# mon.net
KiCad netlist of a schematic drawn in EAGLE
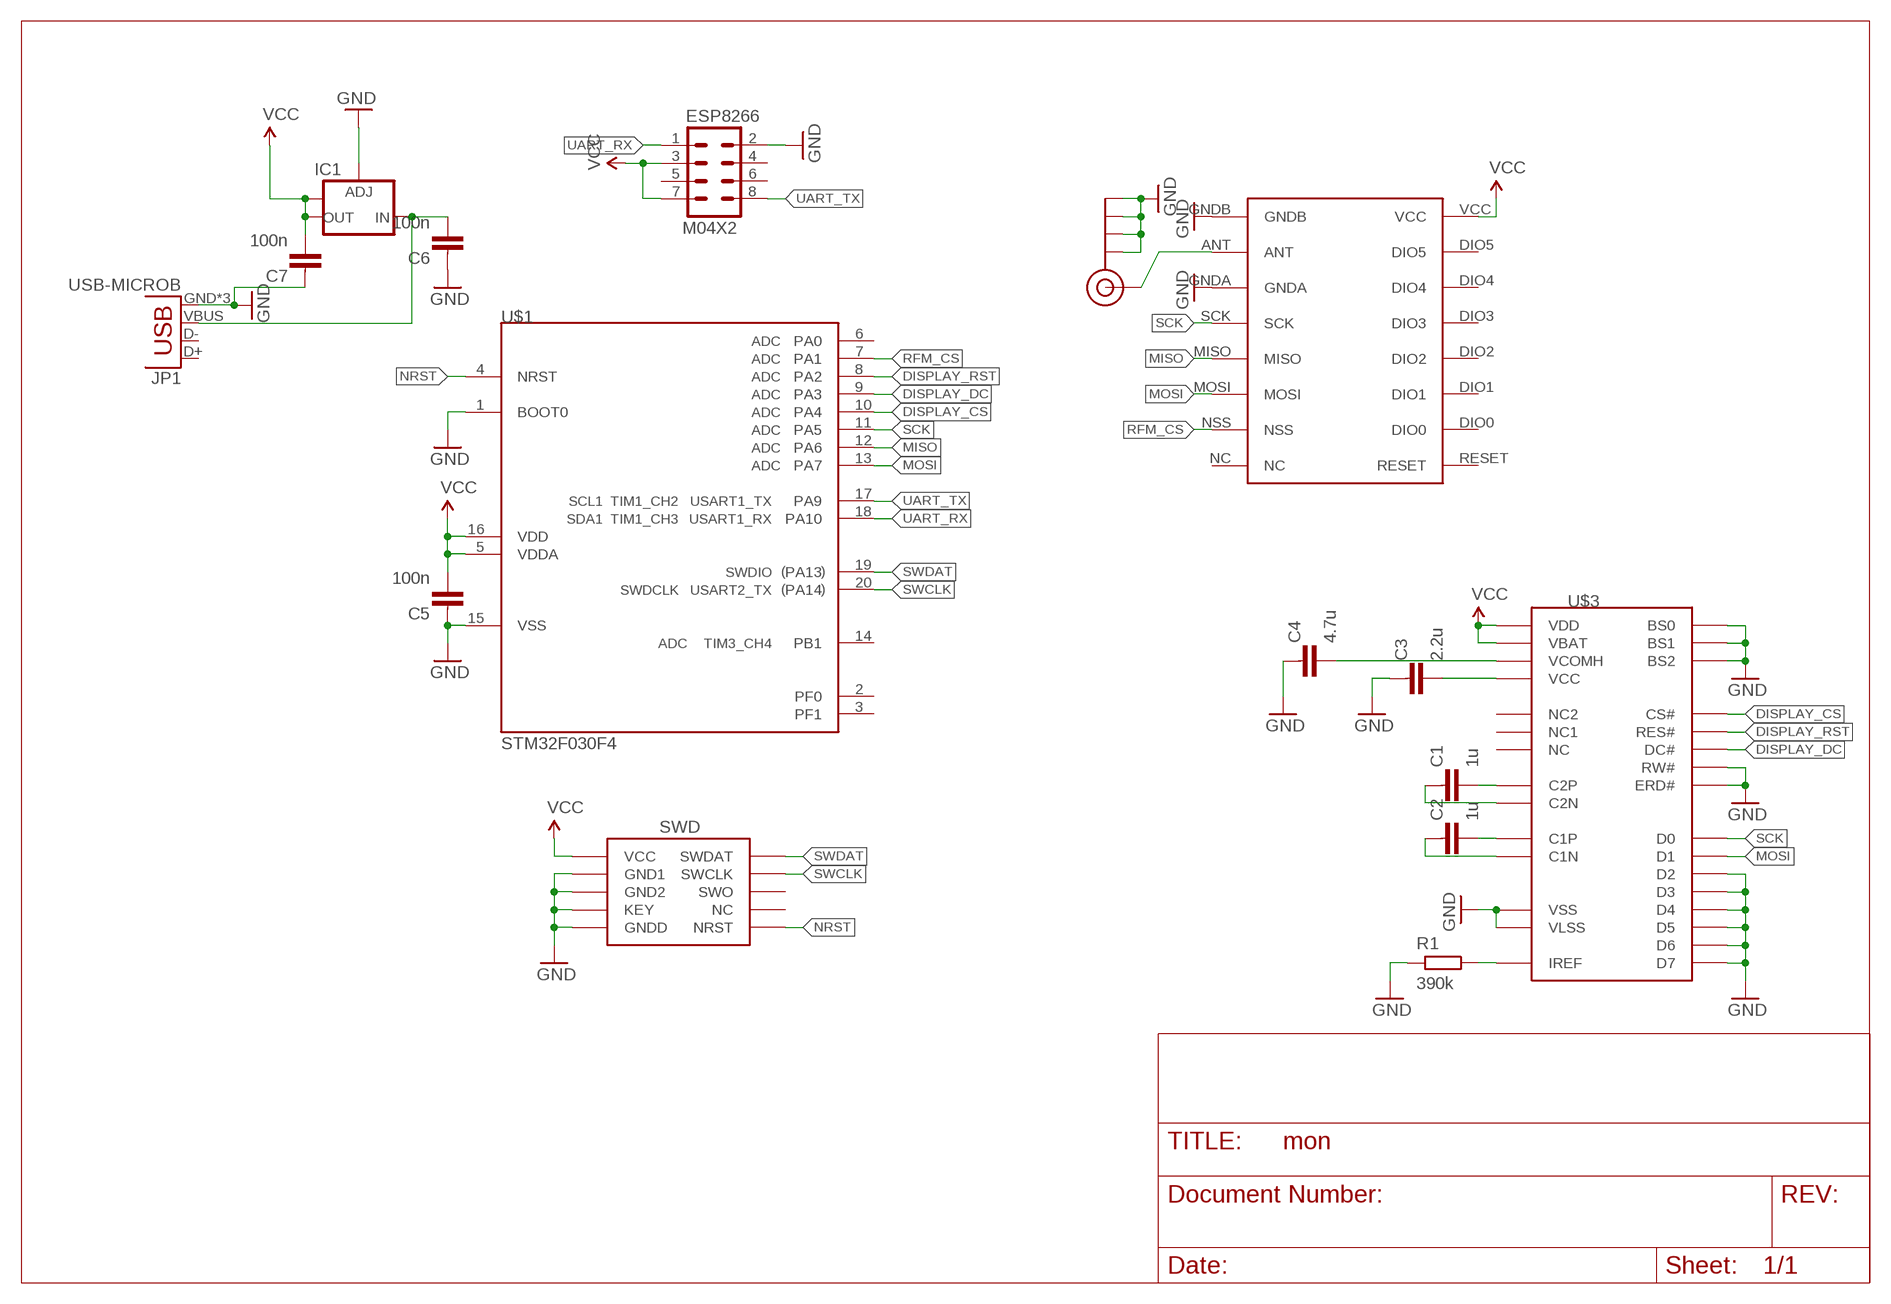
[diagram p0: schematic, sheet 1]

(export (version "E")
  (design (tool "Eeschema 10.0.6"))
  (components
    (comp (ref "C1")
      (value "1u")
      (footprint "eagle-import:C0603-L")
      (libsource (lib "eagle-import") (part "CAPACITOR0603-L"))
    )
    (comp (ref "C2")
      (value "1u")
      (footprint "eagle-import:C0603-L")
      (libsource (lib "eagle-import") (part "CAPACITOR0603-L"))
    )
    (comp (ref "C3")
      (value "2.2u")
      (footprint "eagle-import:C0603-L")
      (libsource (lib "eagle-import") (part "CAPACITOR0603-L"))
    )
    (comp (ref "C4")
      (value "4.7u")
      (footprint "eagle-import:C0603-L")
      (libsource (lib "eagle-import") (part "CAPACITOR0603-L"))
    )
    (comp (ref "C5")
      (value "100n")
      (footprint "eagle-import:C0603-L")
      (libsource (lib "eagle-import") (part "CAPACITOR0603-L"))
    )
    (comp (ref "C6")
      (value "100n")
      (footprint "eagle-import:C0603-L")
      (libsource (lib "eagle-import") (part "CAPACITOR0603-L"))
    )
    (comp (ref "C7")
      (value "100n")
      (footprint "eagle-import:C0603-L")
      (libsource (lib "eagle-import") (part "CAPACITOR0603-L"))
    )
    (comp (ref "ESP8266")
      (value "M04X2")
      (footprint "eagle-import:2X4")
      (libsource (lib "eagle-import") (part "M04X2"))
    )
    (comp (ref "IC1")
      (value "V_REG_LM1117SOT223")
      (footprint "eagle-import:SOT223")
      (libsource (lib "eagle-import") (part "V_REG_LM1117SOT223"))
    )
    (comp (ref "J$1")
      (value "SMA_EDGE")
      (footprint "eagle-import:SMA-EDGE")
      (libsource (lib "eagle-import") (part "SMA_EDGE"))
    )
    (comp (ref "JP1")
      (value "USB-MICROB")
      (footprint "eagle-import:USB-MICROB")
      (libsource (lib "eagle-import") (part "USB-MICROB"))
    )
    (comp (ref "R1")
      (value "390k")
      (footprint "eagle-import:R0603-L")
      (libsource (lib "eagle-import") (part "RESISTOR0603-L"))
    )
    (comp (ref "U$1")
      (value "STM32F030F4")
      (footprint "eagle-import:TSSOP20")
      (libsource (lib "eagle-import") (part "STM32F030F4"))
    )
    (comp (ref "U$2")
      (value "RFM69HW")
      (footprint "eagle-import:RFM")
      (libsource (lib "eagle-import") (part "RFM69HW"))
    )
    (comp (ref "U$3")
      (value "096_INCH_MONOCHROME_DISP")
      (footprint "eagle-import:096_INCH_MONOCHROME_DISP")
      (libsource (lib "eagle-import") (part "096_INCH_MONOCHROME_DISP"))
    )
    (comp (ref "U$4")
      (value "SWD_SHROUD_SMD")
      (footprint "eagle-import:SWD_SMD_SHROUD")
      (libsource (lib "eagle-import") (part "SWD_SHROUD_SMD"))
    )
  )
  (nets
    (net (code "1") (name "DISPLAY_CS") (class "Default")
      (node (ref "U$1") (pin "10") (pinfunction "PA4_10") (pintype "bidirectional"))
      (node (ref "U$3") (pin "P$13") (pinfunction "CS#_P$13") (pintype "bidirectional"))
    )
    (net (code "2") (name "DISPLAY_DC") (class "Default")
      (node (ref "U$1") (pin "9") (pinfunction "PA3_9") (pintype "bidirectional"))
      (node (ref "U$3") (pin "P$15") (pinfunction "DC#_P$15") (pintype "bidirectional"))
    )
    (net (code "3") (name "DISPLAY_RST") (class "Default")
      (node (ref "U$1") (pin "8") (pinfunction "PA2_8") (pintype "bidirectional"))
      (node (ref "U$3") (pin "P$14") (pinfunction "RES#_P$14") (pintype "bidirectional"))
    )
    (net (code "4") (name "GND") (class "Default")
      (node (ref "C3") (pin "1") (pinfunction "1_1") (pintype "passive"))
      (node (ref "C4") (pin "1") (pinfunction "1_1") (pintype "passive"))
      (node (ref "C5") (pin "1") (pinfunction "1_1") (pintype "passive"))
      (node (ref "C6") (pin "1") (pinfunction "1_1") (pintype "passive"))
      (node (ref "C7") (pin "1") (pinfunction "1_1") (pintype "passive"))
      (node (ref "ESP8266") (pin "2") (pinfunction "2_2") (pintype "passive"))
      (node (ref "IC1") (pin "1") (pinfunction "ADJ_1") (pintype "input"))
      (node (ref "J$1") (pin "GND@0") (pinfunction "GND_GND@0") (pintype "bidirectional"))
      (node (ref "J$1") (pin "GND@1") (pinfunction "GND_GND@1") (pintype "bidirectional"))
      (node (ref "J$1") (pin "GND@2") (pinfunction "GND_GND@2") (pintype "bidirectional"))
      (node (ref "J$1") (pin "GND@3") (pinfunction "GND_GND@3") (pintype "bidirectional"))
      (node (ref "JP1") (pin "GND") (pinfunction "GND_GND") (pintype "bidirectional"))
      (node (ref "JP1") (pin "MT1") (pinfunction "GND_MT1") (pintype "bidirectional"))
      (node (ref "JP1") (pin "MT2") (pinfunction "GND_MT2") (pintype "bidirectional"))
      (node (ref "R1") (pin "1") (pinfunction "P$1_1") (pintype "passive"))
      (node (ref "U$1") (pin "1") (pinfunction "BOOT0_1") (pintype "input"))
      (node (ref "U$1") (pin "15") (pinfunction "VSS_15") (pintype "power_in"))
      (node (ref "U$2") (pin "GNDA") (pinfunction "GNDA_GNDA") (pintype "bidirectional"))
      (node (ref "U$2") (pin "GNDB") (pinfunction "GNDB_GNDB") (pintype "bidirectional"))
      (node (ref "U$3") (pin "P$10") (pinfunction "BS0_P$10") (pintype "bidirectional"))
      (node (ref "U$3") (pin "P$11") (pinfunction "BS1_P$11") (pintype "bidirectional"))
      (node (ref "U$3") (pin "P$12") (pinfunction "BS2_P$12") (pintype "bidirectional"))
      (node (ref "U$3") (pin "P$16") (pinfunction "RW#_P$16") (pintype "bidirectional"))
      (node (ref "U$3") (pin "P$17") (pinfunction "ERD#_P$17") (pintype "bidirectional"))
      (node (ref "U$3") (pin "P$20") (pinfunction "D2_P$20") (pintype "bidirectional"))
      (node (ref "U$3") (pin "P$21") (pinfunction "D3_P$21") (pintype "bidirectional"))
      (node (ref "U$3") (pin "P$22") (pinfunction "D4_P$22") (pintype "bidirectional"))
      (node (ref "U$3") (pin "P$23") (pinfunction "D5_P$23") (pintype "bidirectional"))
      (node (ref "U$3") (pin "P$24") (pinfunction "D6_P$24") (pintype "bidirectional"))
      (node (ref "U$3") (pin "P$25") (pinfunction "D7_P$25") (pintype "bidirectional"))
      (node (ref "U$3") (pin "P$29") (pinfunction "VLSS_P$29") (pintype "bidirectional"))
      (node (ref "U$3") (pin "P$8") (pinfunction "VSS_P$8") (pintype "bidirectional"))
      (node (ref "U$4") (pin "3") (pinfunction "GND1_3") (pintype "power_in"))
      (node (ref "U$4") (pin "5") (pinfunction "GND2_5") (pintype "power_in"))
      (node (ref "U$4") (pin "7") (pinfunction "KEY_7") (pintype "bidirectional"))
      (node (ref "U$4") (pin "9") (pinfunction "GNDD_9") (pintype "power_in"))
    )
    (net (code "5") (name "MISO") (class "Default")
      (node (ref "U$1") (pin "12") (pinfunction "PA6_12") (pintype "bidirectional"))
      (node (ref "U$2") (pin "MISO") (pinfunction "MISO_MISO") (pintype "bidirectional"))
    )
    (net (code "6") (name "MOSI") (class "Default")
      (node (ref "U$1") (pin "13") (pinfunction "PA7_13") (pintype "bidirectional"))
      (node (ref "U$2") (pin "MOSI") (pinfunction "MOSI_MOSI") (pintype "bidirectional"))
      (node (ref "U$3") (pin "P$19") (pinfunction "D1_P$19") (pintype "bidirectional"))
    )
    (net (code "7") (name "NRST") (class "Default")
      (node (ref "U$1") (pin "4") (pinfunction "NRST_4") (pintype "input"))
      (node (ref "U$4") (pin "10") (pinfunction "NRST_10") (pintype "bidirectional"))
    )
    (net (code "8") (name "Net-(IC1-IN)") (class "Default")
      (node (ref "C6") (pin "2") (pinfunction "2_2") (pintype "passive"))
      (node (ref "IC1") (pin "3") (pinfunction "IN_3") (pintype "input"))
      (node (ref "JP1") (pin "VBUS") (pinfunction "VBUS_VBUS") (pintype "bidirectional"))
    )
    (net (code "9") (name "Net-(J$1-SIGNAL)") (class "Default")
      (node (ref "J$1") (pin "SIG") (pinfunction "SIGNAL_SIG") (pintype "bidirectional"))
      (node (ref "U$2") (pin "ANT") (pinfunction "ANT_ANT") (pintype "bidirectional"))
    )
    (net (code "10") (name "Net-(R1-P$2)") (class "Default")
      (node (ref "R1") (pin "2") (pinfunction "P$2_2") (pintype "passive"))
      (node (ref "U$3") (pin "P$26") (pinfunction "IREF_P$26") (pintype "bidirectional"))
    )
    (net (code "11") (name "Net-(U$3-C1N)") (class "Default")
      (node (ref "C2") (pin "1") (pinfunction "1_1") (pintype "passive"))
      (node (ref "U$3") (pin "P$5") (pinfunction "C1N_P$5") (pintype "bidirectional"))
    )
    (net (code "12") (name "Net-(U$3-C1P)") (class "Default")
      (node (ref "C2") (pin "2") (pinfunction "2_2") (pintype "passive"))
      (node (ref "U$3") (pin "P$4") (pinfunction "C1P_P$4") (pintype "bidirectional"))
    )
    (net (code "13") (name "Net-(U$3-C2N)") (class "Default")
      (node (ref "C1") (pin "1") (pinfunction "1_1") (pintype "passive"))
      (node (ref "U$3") (pin "P$3") (pinfunction "C2N_P$3") (pintype "bidirectional"))
    )
    (net (code "14") (name "Net-(U$3-C2P)") (class "Default")
      (node (ref "C1") (pin "2") (pinfunction "2_2") (pintype "passive"))
      (node (ref "U$3") (pin "P$2") (pinfunction "C2P_P$2") (pintype "bidirectional"))
    )
    (net (code "15") (name "Net-(U$3-VCC)") (class "Default")
      (node (ref "C3") (pin "2") (pinfunction "2_2") (pintype "passive"))
      (node (ref "U$3") (pin "P$28") (pinfunction "VCC_P$28") (pintype "bidirectional"))
    )
    (net (code "16") (name "Net-(U$3-VCOMH)") (class "Default")
      (node (ref "C4") (pin "2") (pinfunction "2_2") (pintype "passive"))
      (node (ref "U$3") (pin "P$27") (pinfunction "VCOMH_P$27") (pintype "bidirectional"))
    )
    (net (code "17") (name "RFM_CS") (class "Default")
      (node (ref "U$1") (pin "7") (pinfunction "PA1_7") (pintype "bidirectional"))
      (node (ref "U$2") (pin "NSS") (pinfunction "NSS_NSS") (pintype "bidirectional"))
    )
    (net (code "18") (name "SCK") (class "Default")
      (node (ref "U$1") (pin "11") (pinfunction "PA5_11") (pintype "bidirectional"))
      (node (ref "U$2") (pin "SCK") (pinfunction "SCK_SCK") (pintype "bidirectional"))
      (node (ref "U$3") (pin "P$18") (pinfunction "D0_P$18") (pintype "bidirectional"))
    )
    (net (code "19") (name "SWCLK") (class "Default")
      (node (ref "U$1") (pin "20") (pinfunction "PA14_20") (pintype "bidirectional"))
      (node (ref "U$4") (pin "4") (pinfunction "SWCLK_4") (pintype "bidirectional"))
    )
    (net (code "20") (name "SWDAT") (class "Default")
      (node (ref "U$1") (pin "19") (pinfunction "PA13_19") (pintype "bidirectional"))
      (node (ref "U$4") (pin "2") (pinfunction "SWDAT_2") (pintype "bidirectional"))
    )
    (net (code "21") (name "UART_RX") (class "Default")
      (node (ref "ESP8266") (pin "1") (pinfunction "1_1") (pintype "passive"))
      (node (ref "U$1") (pin "18") (pinfunction "PA10_18") (pintype "bidirectional"))
    )
    (net (code "22") (name "UART_TX") (class "Default")
      (node (ref "ESP8266") (pin "8") (pinfunction "8_8") (pintype "passive"))
      (node (ref "U$1") (pin "17") (pinfunction "PA9_17") (pintype "bidirectional"))
    )
    (net (code "23") (name "VCC") (class "Default")
      (node (ref "C5") (pin "2") (pinfunction "2_2") (pintype "passive"))
      (node (ref "C7") (pin "2") (pinfunction "2_2") (pintype "passive"))
      (node (ref "ESP8266") (pin "3") (pinfunction "3_3") (pintype "passive"))
      (node (ref "ESP8266") (pin "7") (pinfunction "7_7") (pintype "passive"))
      (node (ref "IC1") (pin "2") (pinfunction "OUT_2") (pintype "output"))
      (node (ref "IC1") (pin "4") (pinfunction "OUT_4") (pintype "output"))
      (node (ref "U$1") (pin "16") (pinfunction "VDD_16") (pintype "power_in"))
      (node (ref "U$1") (pin "5") (pinfunction "VDDA_5") (pintype "power_in"))
      (node (ref "U$2") (pin "VCC") (pinfunction "VCC_VCC") (pintype "bidirectional"))
      (node (ref "U$3") (pin "P$6") (pinfunction "VBAT_P$6") (pintype "bidirectional"))
      (node (ref "U$3") (pin "P$9") (pinfunction "VDD_P$9") (pintype "bidirectional"))
      (node (ref "U$4") (pin "1") (pinfunction "VCC_1") (pintype "power_in"))
    )
    (net (code "24") (name "unconnected-(ESP8266-Pad4)") (class "Default")
      (node (ref "ESP8266") (pin "4") (pinfunction "4_4") (pintype "passive"))
    )
    (net (code "25") (name "unconnected-(ESP8266-Pad5)") (class "Default")
      (node (ref "ESP8266") (pin "5") (pinfunction "5_5") (pintype "passive"))
    )
    (net (code "26") (name "unconnected-(ESP8266-Pad6)") (class "Default")
      (node (ref "ESP8266") (pin "6") (pinfunction "6_6") (pintype "passive"))
    )
    (net (code "27") (name "unconnected-(JP1-PadD+)") (class "Default")
      (node (ref "JP1") (pin "D+") (pinfunction "D+_D+") (pintype "bidirectional"))
    )
    (net (code "28") (name "unconnected-(JP1-PadD-)") (class "Default")
      (node (ref "JP1") (pin "D-") (pinfunction "D-_D-") (pintype "bidirectional"))
    )
    (net (code "29") (name "unconnected-(U$1-PA0-Pad6)") (class "Default")
      (node (ref "U$1") (pin "6") (pinfunction "PA0_6") (pintype "bidirectional"))
    )
    (net (code "30") (name "unconnected-(U$1-PB1-Pad14)") (class "Default")
      (node (ref "U$1") (pin "14") (pinfunction "PB1_14") (pintype "bidirectional"))
    )
    (net (code "31") (name "unconnected-(U$1-PF0-Pad2)") (class "Default")
      (node (ref "U$1") (pin "2") (pinfunction "PF0_2") (pintype "bidirectional"))
    )
    (net (code "32") (name "unconnected-(U$1-PF1-Pad3)") (class "Default")
      (node (ref "U$1") (pin "3") (pinfunction "PF1_3") (pintype "bidirectional"))
    )
    (net (code "33") (name "unconnected-(U$2-PadDIO0)") (class "Default")
      (node (ref "U$2") (pin "DIO0") (pinfunction "DIO0_DIO0") (pintype "bidirectional"))
    )
    (net (code "34") (name "unconnected-(U$2-PadDIO1)") (class "Default")
      (node (ref "U$2") (pin "DIO1") (pinfunction "DIO1_DIO1") (pintype "bidirectional"))
    )
    (net (code "35") (name "unconnected-(U$2-PadDIO2)") (class "Default")
      (node (ref "U$2") (pin "DIO2") (pinfunction "DIO2_DIO2") (pintype "bidirectional"))
    )
    (net (code "36") (name "unconnected-(U$2-PadDIO3)") (class "Default")
      (node (ref "U$2") (pin "DIO3") (pinfunction "DIO3_DIO3") (pintype "bidirectional"))
    )
    (net (code "37") (name "unconnected-(U$2-PadDIO4)") (class "Default")
      (node (ref "U$2") (pin "DIO4") (pinfunction "DIO4_DIO4") (pintype "bidirectional"))
    )
    (net (code "38") (name "unconnected-(U$2-PadDIO5)") (class "Default")
      (node (ref "U$2") (pin "DIO5") (pinfunction "DIO5_DIO5") (pintype "bidirectional"))
    )
    (net (code "39") (name "unconnected-(U$2-PadNC)") (class "Default")
      (node (ref "U$2") (pin "NC") (pinfunction "NC_NC") (pintype "bidirectional"))
    )
    (net (code "40") (name "unconnected-(U$2-PadRESET)") (class "Default")
      (node (ref "U$2") (pin "RESET") (pinfunction "RESET_RESET") (pintype "bidirectional"))
    )
    (net (code "41") (name "unconnected-(U$3-NC-PadP$1)") (class "Default")
      (node (ref "U$3") (pin "P$1") (pinfunction "NC_P$1") (pintype "no_connect"))
    )
    (net (code "42") (name "unconnected-(U$3-NC1-PadP$7)") (class "Default")
      (node (ref "U$3") (pin "P$7") (pinfunction "NC1_P$7") (pintype "no_connect"))
    )
    (net (code "43") (name "unconnected-(U$3-NC2-PadP$30)") (class "Default")
      (node (ref "U$3") (pin "P$30") (pinfunction "NC2_P$30") (pintype "no_connect"))
    )
    (net (code "44") (name "unconnected-(U$4-NC-Pad8)") (class "Default")
      (node (ref "U$4") (pin "8") (pinfunction "NC_8") (pintype "no_connect"))
    )
    (net (code "45") (name "unconnected-(U$4-SWO-Pad6)") (class "Default")
      (node (ref "U$4") (pin "6") (pinfunction "SWO_6") (pintype "bidirectional"))
    )
  )
)
